# Banks_5_6.net
KiCad netlist of a schematic drawn in Altium Designer
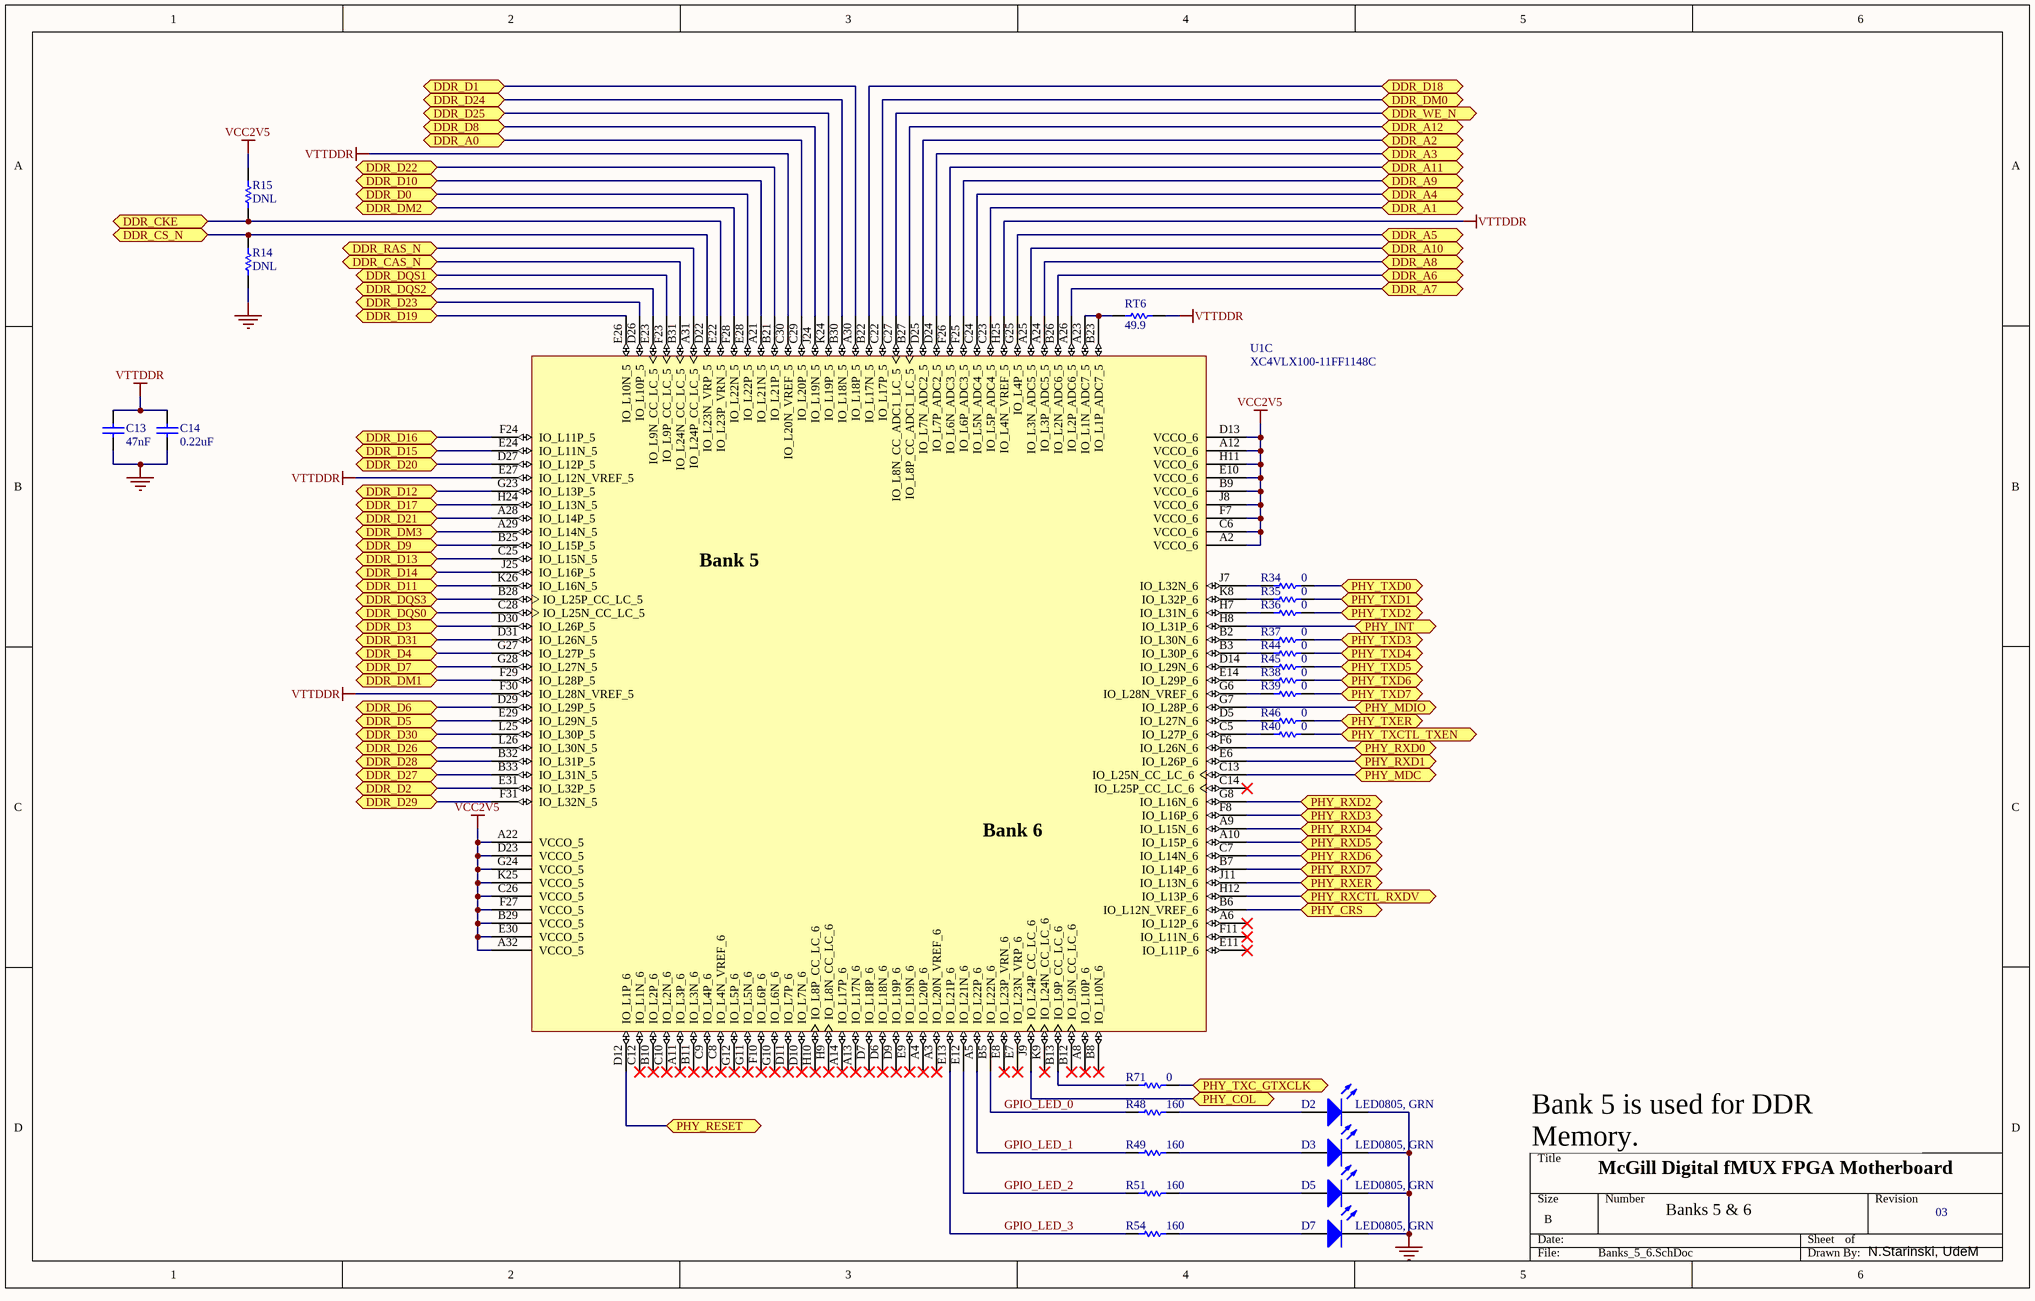
[diagram p0: Banks_5_6.SchDoc]

(export (version "E")
  (design (tool "Eeschema 10.0.6"))
  (components
    (comp (ref "C13")
      (value "47nF")
      (footprint "CC1005-0402")
      (description "Capacitor (Semiconductor SIM Model)")
      (fields (field (name "PUBLISHER") "Altium Limited"))
      (libsource (lib "Miscellaneous Devices") (part "Cap Semi"))
    )
    (comp (ref "C14")
      (value "0.22uF")
      (footprint "CC1608-0603")
      (description "Capacitor (Semiconductor SIM Model)")
      (fields (field (name "PUBLISHER") "Altium Limited"))
      (libsource (lib "Miscellaneous Devices") (part "Cap Semi"))
    )
    (comp (ref "D2")
      (value "LED0805, GRN")
      (footprint "SMD _LED")
      (description "LED 0805 LTST-C170GKT")
      (fields (field (name "PUBLISHER") "Altium Limited"))
      (libsource (lib "Miscellaneous Devices") (part "LED3"))
    )
    (comp (ref "D3")
      (value "LED0805, GRN")
      (footprint "SMD _LED")
      (description "LED 0805 LTST-C170GKT")
      (fields (field (name "PUBLISHER") "Altium Limited"))
      (libsource (lib "Miscellaneous Devices") (part "LED3"))
    )
    (comp (ref "D5")
      (value "LED0805, GRN")
      (footprint "SMD _LED")
      (description "LED 0805 LTST-C170GKT")
      (fields (field (name "PUBLISHER") "Altium Limited"))
      (libsource (lib "Miscellaneous Devices") (part "LED3"))
    )
    (comp (ref "D7")
      (value "LED0805, GRN")
      (footprint "SMD _LED")
      (description "LED 0805 LTST-C170GKT")
      (fields (field (name "PUBLISHER") "Altium Limited"))
      (libsource (lib "Miscellaneous Devices") (part "LED3"))
    )
    (comp (ref "R14")
      (value "DNL")
      (footprint "CR1608-0603")
      (description "Semiconductor Resistor")
      (fields (field (name "PUBLISHER") "Altium Limited"))
      (libsource (lib "Miscellaneous Devices 02") (part "Res Semi"))
    )
    (comp (ref "R15")
      (value "DNL")
      (footprint "CR1608-0603")
      (description "Semiconductor Resistor")
      (fields (field (name "PUBLISHER") "Altium Limited"))
      (libsource (lib "Miscellaneous Devices 02") (part "Res Semi"))
    )
    (comp (ref "R34")
      (value "0")
      (footprint "CR1608-0603")
      (description "Resistor 0603")
      (fields (field (name "PUBLISHER") "Altium Limited"))
      (libsource (lib "Miscellaneous Devices") (part "Res Semi"))
    )
    (comp (ref "R35")
      (value "0")
      (footprint "CR1608-0603")
      (description "Resistor 0603")
      (fields (field (name "PUBLISHER") "Altium Limited"))
      (libsource (lib "Miscellaneous Devices") (part "Res Semi"))
    )
    (comp (ref "R36")
      (value "0")
      (footprint "CR1608-0603")
      (description "Resistor 0603")
      (fields (field (name "PUBLISHER") "Altium Limited"))
      (libsource (lib "Miscellaneous Devices") (part "Res Semi"))
    )
    (comp (ref "R37")
      (value "0")
      (footprint "CR1608-0603")
      (description "Resistor 0603")
      (fields (field (name "PUBLISHER") "Altium Limited"))
      (libsource (lib "Miscellaneous Devices") (part "Res Semi"))
    )
    (comp (ref "R38")
      (value "0")
      (footprint "CR1608-0603")
      (description "Resistor 0603")
      (fields (field (name "PUBLISHER") "Altium Limited"))
      (libsource (lib "Miscellaneous Devices") (part "Res Semi"))
    )
    (comp (ref "R39")
      (value "0")
      (footprint "CR1608-0603")
      (description "Resistor 0603")
      (fields (field (name "PUBLISHER") "Altium Limited"))
      (libsource (lib "Miscellaneous Devices") (part "Res Semi"))
    )
    (comp (ref "R40")
      (value "0")
      (footprint "CR1608-0603")
      (description "Resistor 0603")
      (fields (field (name "PUBLISHER") "Altium Limited"))
      (libsource (lib "Miscellaneous Devices") (part "Res Semi"))
    )
    (comp (ref "R44")
      (value "0")
      (footprint "CR1608-0603")
      (description "Resistor 0603")
      (fields (field (name "PUBLISHER") "Altium Limited"))
      (libsource (lib "Miscellaneous Devices") (part "Res Semi"))
    )
    (comp (ref "R45")
      (value "0")
      (footprint "CR1608-0603")
      (description "Resistor 0603")
      (fields (field (name "PUBLISHER") "Altium Limited"))
      (libsource (lib "Miscellaneous Devices") (part "Res Semi"))
    )
    (comp (ref "R46")
      (value "0")
      (footprint "CR1608-0603")
      (description "Resistor 0603")
      (fields (field (name "PUBLISHER") "Altium Limited"))
      (libsource (lib "Miscellaneous Devices") (part "Res Semi"))
    )
    (comp (ref "R48")
      (value "160")
      (footprint "CR1608-0603")
      (description "Resistor 0603")
      (fields (field (name "PUBLISHER") "Altium Limited"))
      (libsource (lib "Miscellaneous Devices") (part "Res Semi"))
    )
    (comp (ref "R49")
      (value "160")
      (footprint "CR1608-0603")
      (description "Resistor 0603")
      (fields (field (name "PUBLISHER") "Altium Limited"))
      (libsource (lib "Miscellaneous Devices") (part "Res Semi"))
    )
    (comp (ref "R51")
      (value "160")
      (footprint "CR1608-0603")
      (description "Resistor 0603")
      (fields (field (name "PUBLISHER") "Altium Limited"))
      (libsource (lib "Miscellaneous Devices") (part "Res Semi"))
    )
    (comp (ref "R54")
      (value "160")
      (footprint "CR1608-0603")
      (description "Resistor 0603")
      (fields (field (name "PUBLISHER") "Altium Limited"))
      (libsource (lib "Miscellaneous Devices") (part "Res Semi"))
    )
    (comp (ref "R71")
      (value "0")
      (footprint "CR1608-0603")
      (description "Resistor 0603")
      (fields (field (name "PUBLISHER") "Altium Limited"))
      (libsource (lib "Miscellaneous Devices") (part "Res Semi"))
    )
    (comp (ref "RT6")
      (value "49.9")
      (footprint "CR1608-0603")
      (description "Resistor 0603")
      (fields (field (name "PUBLISHER") "Altium Limited"))
      (libsource (lib "Miscellaneous Devices 02") (part "Res Semi"))
    )
    (comp (ref "U1")
      (value "XC4VLX100-11FF1148C")
      (footprint "FF1148")
      (description "Xilinx Virtex-4 LX Platform FPGA, 1148-Ball FFBGA, Speed Grade 11, 768 User I/Os, Commercial Grade")
      (fields (field (name "PUBLISHER") "Altium Limited"))
      (libsource (lib "Xilinx Virtex-4") (part "XC4VLX100-11FF1148C"))
    )
  )
  (nets
    (net (code "1") (name "/DDR_A0") (class "Default")
      (node (ref "U1") (pin "C29") (pinfunction "IO_L20P_5_C29") (pintype "bidirectional"))
    )
    (net (code "2") (name "/DDR_A1") (class "Default")
      (node (ref "U1") (pin "C23") (pinfunction "IO_L5P_ADC4_5_C23") (pintype "bidirectional"))
    )
    (net (code "3") (name "/DDR_A2") (class "Default")
      (node (ref "U1") (pin "D25") (pinfunction "IO_L7N_ADC2_5_D25") (pintype "bidirectional"))
    )
    (net (code "4") (name "/DDR_A3") (class "Default")
      (node (ref "U1") (pin "D24") (pinfunction "IO_L7P_ADC2_5_D24") (pintype "bidirectional"))
    )
    (net (code "5") (name "/DDR_A4") (class "Default")
      (node (ref "U1") (pin "C24") (pinfunction "IO_L5N_ADC4_5_C24") (pintype "bidirectional"))
    )
    (net (code "6") (name "/DDR_A5") (class "Default")
      (node (ref "U1") (pin "G25") (pinfunction "IO_L4P_5_G25") (pintype "bidirectional"))
    )
    (net (code "7") (name "/DDR_A6") (class "Default")
      (node (ref "U1") (pin "B26") (pinfunction "IO_L2N_ADC6_5_B26") (pintype "bidirectional"))
    )
    (net (code "8") (name "/DDR_A7") (class "Default")
      (node (ref "U1") (pin "A26") (pinfunction "IO_L2P_ADC6_5_A26") (pintype "bidirectional"))
    )
    (net (code "9") (name "/DDR_A8") (class "Default")
      (node (ref "U1") (pin "A24") (pinfunction "IO_L3P_ADC5_5_A24") (pintype "bidirectional"))
    )
    (net (code "10") (name "/DDR_A9") (class "Default")
      (node (ref "U1") (pin "F25") (pinfunction "IO_L6P_ADC3_5_F25") (pintype "bidirectional"))
    )
    (net (code "11") (name "/DDR_A10") (class "Default")
      (node (ref "U1") (pin "A25") (pinfunction "IO_L3N_ADC5_5_A25") (pintype "bidirectional"))
    )
    (net (code "12") (name "/DDR_A11") (class "Default")
      (node (ref "U1") (pin "F26") (pinfunction "IO_L6N_ADC3_5_F26") (pintype "bidirectional"))
    )
    (net (code "13") (name "/DDR_A12") (class "Default")
      (node (ref "U1") (pin "B27") (pinfunction "IO_L8P_CC_ADC1_LC_5_B27") (pintype "bidirectional"))
    )
    (net (code "14") (name "/DDR_CAS_N") (class "Default")
      (node (ref "U1") (pin "B31") (pinfunction "IO_L24N_CC_LC_5_B31") (pintype "bidirectional"))
    )
    (net (code "15") (name "/DDR_CKE") (class "Default")
      (node (ref "R15") (pin "1") (pinfunction "1_1") (pintype "passive"))
      (node (ref "U1") (pin "E22") (pinfunction "IO_L23P_VRN_5_E22") (pintype "bidirectional"))
    )
    (net (code "16") (name "/DDR_CS_N") (class "Default")
      (node (ref "R14") (pin "2") (pinfunction "2_2") (pintype "passive"))
      (node (ref "U1") (pin "D22") (pinfunction "IO_L23N_VRP_5_D22") (pintype "bidirectional"))
    )
    (net (code "17") (name "/DDR_D0") (class "Default")
      (node (ref "U1") (pin "E28") (pinfunction "IO_L22P_5_E28") (pintype "bidirectional"))
    )
    (net (code "18") (name "/DDR_D1") (class "Default")
      (node (ref "U1") (pin "A30") (pinfunction "IO_L18P_5_A30") (pintype "bidirectional"))
    )
    (net (code "19") (name "/DDR_D2") (class "Default")
      (node (ref "U1") (pin "E31") (pinfunction "IO_L32P_5_E31") (pintype "bidirectional"))
    )
    (net (code "20") (name "/DDR_D3") (class "Default")
      (node (ref "U1") (pin "D30") (pinfunction "IO_L26P_5_D30") (pintype "bidirectional"))
    )
    (net (code "21") (name "/DDR_D4") (class "Default")
      (node (ref "U1") (pin "G27") (pinfunction "IO_L27P_5_G27") (pintype "bidirectional"))
    )
    (net (code "22") (name "/DDR_D5") (class "Default")
      (node (ref "U1") (pin "E29") (pinfunction "IO_L29N_5_E29") (pintype "bidirectional"))
    )
    (net (code "23") (name "/DDR_D6") (class "Default")
      (node (ref "U1") (pin "D29") (pinfunction "IO_L29P_5_D29") (pintype "bidirectional"))
    )
    (net (code "24") (name "/DDR_D7") (class "Default")
      (node (ref "U1") (pin "G28") (pinfunction "IO_L27N_5_G28") (pintype "bidirectional"))
    )
    (net (code "25") (name "/DDR_D8") (class "Default")
      (node (ref "U1") (pin "J24") (pinfunction "IO_L19N_5_J24") (pintype "bidirectional"))
    )
    (net (code "26") (name "/DDR_D9") (class "Default")
      (node (ref "U1") (pin "B25") (pinfunction "IO_L15P_5_B25") (pintype "bidirectional"))
    )
    (net (code "27") (name "/DDR_D10") (class "Default")
      (node (ref "U1") (pin "A21") (pinfunction "IO_L21N_5_A21") (pintype "bidirectional"))
    )
    (net (code "28") (name "/DDR_D11") (class "Default")
      (node (ref "U1") (pin "K26") (pinfunction "IO_L16N_5_K26") (pintype "bidirectional"))
    )
    (net (code "29") (name "/DDR_D12") (class "Default")
      (node (ref "U1") (pin "G23") (pinfunction "IO_L13P_5_G23") (pintype "bidirectional"))
    )
    (net (code "30") (name "/DDR_D13") (class "Default")
      (node (ref "U1") (pin "C25") (pinfunction "IO_L15N_5_C25") (pintype "bidirectional"))
    )
    (net (code "31") (name "/DDR_D14") (class "Default")
      (node (ref "U1") (pin "J25") (pinfunction "IO_L16P_5_J25") (pintype "bidirectional"))
    )
    (net (code "32") (name "/DDR_D15") (class "Default")
      (node (ref "U1") (pin "E24") (pinfunction "IO_L11N_5_E24") (pintype "bidirectional"))
    )
    (net (code "33") (name "/DDR_D16") (class "Default")
      (node (ref "U1") (pin "F24") (pinfunction "IO_L11P_5_F24") (pintype "bidirectional"))
    )
    (net (code "34") (name "/DDR_D17") (class "Default")
      (node (ref "U1") (pin "H24") (pinfunction "IO_L13N_5_H24") (pintype "bidirectional"))
    )
    (net (code "35") (name "/DDR_D18") (class "Default")
      (node (ref "U1") (pin "B22") (pinfunction "IO_L17N_5_B22") (pintype "bidirectional"))
    )
    (net (code "36") (name "/DDR_D19") (class "Default")
      (node (ref "U1") (pin "E26") (pinfunction "IO_L10N_5_E26") (pintype "bidirectional"))
    )
    (net (code "37") (name "/DDR_D20") (class "Default")
      (node (ref "U1") (pin "D27") (pinfunction "IO_L12P_5_D27") (pintype "bidirectional"))
    )
    (net (code "38") (name "/DDR_D21") (class "Default")
      (node (ref "U1") (pin "A28") (pinfunction "IO_L14P_5_A28") (pintype "bidirectional"))
    )
    (net (code "39") (name "/DDR_D22") (class "Default")
      (node (ref "U1") (pin "B21") (pinfunction "IO_L21P_5_B21") (pintype "bidirectional"))
    )
    (net (code "40") (name "/DDR_D23") (class "Default")
      (node (ref "U1") (pin "D26") (pinfunction "IO_L10P_5_D26") (pintype "bidirectional"))
    )
    (net (code "41") (name "/DDR_D24") (class "Default")
      (node (ref "U1") (pin "B30") (pinfunction "IO_L18N_5_B30") (pintype "bidirectional"))
    )
    (net (code "42") (name "/DDR_D25") (class "Default")
      (node (ref "U1") (pin "K24") (pinfunction "IO_L19P_5_K24") (pintype "bidirectional"))
    )
    (net (code "43") (name "/DDR_D26") (class "Default")
      (node (ref "U1") (pin "L26") (pinfunction "IO_L30N_5_L26") (pintype "bidirectional"))
    )
    (net (code "44") (name "/DDR_D27") (class "Default")
      (node (ref "U1") (pin "B33") (pinfunction "IO_L31N_5_B33") (pintype "bidirectional"))
    )
    (net (code "45") (name "/DDR_D28") (class "Default")
      (node (ref "U1") (pin "B32") (pinfunction "IO_L31P_5_B32") (pintype "bidirectional"))
    )
    (net (code "46") (name "/DDR_D29") (class "Default")
      (node (ref "U1") (pin "F31") (pinfunction "IO_L32N_5_F31") (pintype "bidirectional"))
    )
    (net (code "47") (name "/DDR_D30") (class "Default")
      (node (ref "U1") (pin "L25") (pinfunction "IO_L30P_5_L25") (pintype "bidirectional"))
    )
    (net (code "48") (name "/DDR_D31") (class "Default")
      (node (ref "U1") (pin "D31") (pinfunction "IO_L26N_5_D31") (pintype "bidirectional"))
    )
    (net (code "49") (name "/DDR_DM0") (class "Default")
      (node (ref "U1") (pin "C22") (pinfunction "IO_L17P_5_C22") (pintype "bidirectional"))
    )
    (net (code "50") (name "/DDR_DM1") (class "Default")
      (node (ref "U1") (pin "F29") (pinfunction "IO_L28P_5_F29") (pintype "bidirectional"))
    )
    (net (code "51") (name "/DDR_DM2") (class "Default")
      (node (ref "U1") (pin "F28") (pinfunction "IO_L22N_5_F28") (pintype "bidirectional"))
    )
    (net (code "52") (name "/DDR_DM3") (class "Default")
      (node (ref "U1") (pin "A29") (pinfunction "IO_L14N_5_A29") (pintype "bidirectional"))
    )
    (net (code "53") (name "/DDR_DQS0") (class "Default")
      (node (ref "U1") (pin "C28") (pinfunction "IO_L25N_CC_LC_5_C28") (pintype "bidirectional"))
    )
    (net (code "54") (name "/DDR_DQS1") (class "Default")
      (node (ref "U1") (pin "F23") (pinfunction "IO_L9P_CC_LC_5_F23") (pintype "bidirectional"))
    )
    (net (code "55") (name "/DDR_DQS2") (class "Default")
      (node (ref "U1") (pin "E23") (pinfunction "IO_L9N_CC_LC_5_E23") (pintype "bidirectional"))
    )
    (net (code "56") (name "/DDR_DQS3") (class "Default")
      (node (ref "U1") (pin "B28") (pinfunction "IO_L25P_CC_LC_5_B28") (pintype "bidirectional"))
    )
    (net (code "57") (name "/DDR_RAS_N") (class "Default")
      (node (ref "U1") (pin "A31") (pinfunction "IO_L24P_CC_LC_5_A31") (pintype "bidirectional"))
    )
    (net (code "58") (name "/DDR_WE_N") (class "Default")
      (node (ref "U1") (pin "C27") (pinfunction "IO_L8N_CC_ADC1_LC_5_C27") (pintype "bidirectional"))
    )
    (net (code "59") (name "/GPIO_LED_0") (class "Default")
      (node (ref "R48") (pin "1") (pinfunction "1_1") (pintype "passive"))
      (node (ref "U1") (pin "B5") (pinfunction "IO_L22N_6_B5") (pintype "bidirectional"))
    )
    (net (code "60") (name "/GPIO_LED_1") (class "Default")
      (node (ref "R49") (pin "1") (pinfunction "1_1") (pintype "passive"))
      (node (ref "U1") (pin "A5") (pinfunction "IO_L22P_6_A5") (pintype "bidirectional"))
    )
    (net (code "61") (name "/GPIO_LED_2") (class "Default")
      (node (ref "R51") (pin "1") (pinfunction "1_1") (pintype "passive"))
      (node (ref "U1") (pin "E12") (pinfunction "IO_L21N_6_E12") (pintype "bidirectional"))
    )
    (net (code "62") (name "/GPIO_LED_3") (class "Default")
      (node (ref "R54") (pin "1") (pinfunction "1_1") (pintype "passive"))
      (node (ref "U1") (pin "E13") (pinfunction "IO_L21P_6_E13") (pintype "bidirectional"))
    )
    (net (code "63") (name "/PHY_COL") (class "Default")
      (node (ref "U1") (pin "J9") (pinfunction "IO_L24P_CC_LC_6_J9") (pintype "bidirectional"))
    )
    (net (code "64") (name "/PHY_CRS") (class "Default")
      (node (ref "U1") (pin "B6") (pinfunction "IO_L12N_VREF_6_B6") (pintype "bidirectional"))
    )
    (net (code "65") (name "/PHY_INT") (class "Default")
      (node (ref "U1") (pin "H8") (pinfunction "IO_L31P_6_H8") (pintype "bidirectional"))
    )
    (net (code "66") (name "/PHY_MDC") (class "Default")
      (node (ref "U1") (pin "C13") (pinfunction "IO_L25N_CC_LC_6_C13") (pintype "bidirectional"))
    )
    (net (code "67") (name "/PHY_MDIO") (class "Default")
      (node (ref "U1") (pin "G7") (pinfunction "IO_L28P_6_G7") (pintype "bidirectional"))
    )
    (net (code "68") (name "/PHY_RESET") (class "Default")
      (node (ref "U1") (pin "D12") (pinfunction "IO_L1P_6_D12") (pintype "bidirectional"))
    )
    (net (code "69") (name "/PHY_RXCTL_RXDV") (class "Default")
      (node (ref "U1") (pin "H12") (pinfunction "IO_L13P_6_H12") (pintype "bidirectional"))
    )
    (net (code "70") (name "/PHY_RXD0") (class "Default")
      (node (ref "U1") (pin "F6") (pinfunction "IO_L26N_6_F6") (pintype "bidirectional"))
    )
    (net (code "71") (name "/PHY_RXD1") (class "Default")
      (node (ref "U1") (pin "E6") (pinfunction "IO_L26P_6_E6") (pintype "bidirectional"))
    )
    (net (code "72") (name "/PHY_RXD2") (class "Default")
      (node (ref "U1") (pin "G8") (pinfunction "IO_L16N_6_G8") (pintype "bidirectional"))
    )
    (net (code "73") (name "/PHY_RXD3") (class "Default")
      (node (ref "U1") (pin "F8") (pinfunction "IO_L16P_6_F8") (pintype "bidirectional"))
    )
    (net (code "74") (name "/PHY_RXD4") (class "Default")
      (node (ref "U1") (pin "A9") (pinfunction "IO_L15N_6_A9") (pintype "bidirectional"))
    )
    (net (code "75") (name "/PHY_RXD5") (class "Default")
      (node (ref "U1") (pin "A10") (pinfunction "IO_L15P_6_A10") (pintype "bidirectional"))
    )
    (net (code "76") (name "/PHY_RXD6") (class "Default")
      (node (ref "U1") (pin "C7") (pinfunction "IO_L14N_6_C7") (pintype "bidirectional"))
    )
    (net (code "77") (name "/PHY_RXD7") (class "Default")
      (node (ref "U1") (pin "B7") (pinfunction "IO_L14P_6_B7") (pintype "bidirectional"))
    )
    (net (code "78") (name "/PHY_RXER") (class "Default")
      (node (ref "U1") (pin "J11") (pinfunction "IO_L13N_6_J11") (pintype "bidirectional"))
    )
    (net (code "79") (name "/PHY_TXCTL_TXEN") (class "Default")
      (node (ref "R40") (pin "2") (pinfunction "2_2") (pintype "passive"))
    )
    (net (code "80") (name "/PHY_TXC_GTXCLK") (class "Default")
      (node (ref "R71") (pin "2") (pinfunction "2_2") (pintype "passive"))
    )
    (net (code "81") (name "/PHY_TXD0") (class "Default")
      (node (ref "R34") (pin "2") (pinfunction "2_2") (pintype "passive"))
    )
    (net (code "82") (name "/PHY_TXD1") (class "Default")
      (node (ref "R35") (pin "2") (pinfunction "2_2") (pintype "passive"))
    )
    (net (code "83") (name "/PHY_TXD2") (class "Default")
      (node (ref "R36") (pin "2") (pinfunction "2_2") (pintype "passive"))
    )
    (net (code "84") (name "/PHY_TXD3") (class "Default")
      (node (ref "R37") (pin "2") (pinfunction "2_2") (pintype "passive"))
    )
    (net (code "85") (name "/PHY_TXD4") (class "Default")
      (node (ref "R44") (pin "2") (pinfunction "2_2") (pintype "passive"))
    )
    (net (code "86") (name "/PHY_TXD5") (class "Default")
      (node (ref "R45") (pin "2") (pinfunction "2_2") (pintype "passive"))
    )
    (net (code "87") (name "/PHY_TXD6") (class "Default")
      (node (ref "R38") (pin "2") (pinfunction "2_2") (pintype "passive"))
    )
    (net (code "88") (name "/PHY_TXD7") (class "Default")
      (node (ref "R39") (pin "2") (pinfunction "2_2") (pintype "passive"))
    )
    (net (code "89") (name "/PHY_TXER") (class "Default")
      (node (ref "R46") (pin "2") (pinfunction "2_2") (pintype "passive"))
    )
    (net (code "90") (name "GND") (class "Default")
      (node (ref "C13") (pin "1") (pinfunction "1_1") (pintype "passive"))
      (node (ref "C14") (pin "1") (pinfunction "1_1") (pintype "passive"))
      (node (ref "D2") (pin "2") (pinfunction "K_2") (pintype "passive"))
      (node (ref "D3") (pin "2") (pinfunction "K_2") (pintype "passive"))
      (node (ref "D5") (pin "2") (pinfunction "K_2") (pintype "passive"))
      (node (ref "D7") (pin "2") (pinfunction "K_2") (pintype "passive"))
      (node (ref "R14") (pin "1") (pinfunction "1_1") (pintype "passive"))
    )
    (net (code "91") (name "Net-(D2-A)") (class "Default")
      (node (ref "D2") (pin "1") (pinfunction "A_1") (pintype "passive"))
      (node (ref "R48") (pin "2") (pinfunction "2_2") (pintype "passive"))
    )
    (net (code "92") (name "Net-(D3-A)") (class "Default")
      (node (ref "D3") (pin "1") (pinfunction "A_1") (pintype "passive"))
      (node (ref "R49") (pin "2") (pinfunction "2_2") (pintype "passive"))
    )
    (net (code "93") (name "Net-(D5-A)") (class "Default")
      (node (ref "D5") (pin "1") (pinfunction "A_1") (pintype "passive"))
      (node (ref "R51") (pin "2") (pinfunction "2_2") (pintype "passive"))
    )
    (net (code "94") (name "Net-(D7-A)") (class "Default")
      (node (ref "D7") (pin "1") (pinfunction "A_1") (pintype "passive"))
      (node (ref "R54") (pin "2") (pinfunction "2_2") (pintype "passive"))
    )
    (net (code "95") (name "Net-(U1C-IO_L1N_ADC7_5)") (class "Default")
      (node (ref "RT6") (pin "1") (pinfunction "1_1") (pintype "passive"))
      (node (ref "U1") (pin "A23") (pinfunction "IO_L1N_ADC7_5_A23") (pintype "bidirectional"))
      (node (ref "U1") (pin "B23") (pinfunction "IO_L1P_ADC7_5_B23") (pintype "bidirectional"))
    )
    (net (code "96") (name "Net-(U1C-IO_L9P_CC_LC_6)") (class "Default")
      (node (ref "R71") (pin "1") (pinfunction "1_1") (pintype "passive"))
      (node (ref "U1") (pin "B13") (pinfunction "IO_L9P_CC_LC_6_B13") (pintype "bidirectional"))
    )
    (net (code "97") (name "Net-(U1C-IO_L27N_6)") (class "Default")
      (node (ref "R46") (pin "1") (pinfunction "1_1") (pintype "passive"))
      (node (ref "U1") (pin "D5") (pinfunction "IO_L27N_6_D5") (pintype "bidirectional"))
    )
    (net (code "98") (name "Net-(U1C-IO_L27P_6)") (class "Default")
      (node (ref "R40") (pin "1") (pinfunction "1_1") (pintype "passive"))
      (node (ref "U1") (pin "C5") (pinfunction "IO_L27P_6_C5") (pintype "bidirectional"))
    )
    (net (code "99") (name "Net-(U1C-IO_L28N_VREF_6)") (class "Default")
      (node (ref "R39") (pin "1") (pinfunction "1_1") (pintype "passive"))
      (node (ref "U1") (pin "G6") (pinfunction "IO_L28N_VREF_6_G6") (pintype "bidirectional"))
    )
    (net (code "100") (name "Net-(U1C-IO_L29N_6)") (class "Default")
      (node (ref "R45") (pin "1") (pinfunction "1_1") (pintype "passive"))
      (node (ref "U1") (pin "D14") (pinfunction "IO_L29N_6_D14") (pintype "bidirectional"))
    )
    (net (code "101") (name "Net-(U1C-IO_L29P_6)") (class "Default")
      (node (ref "R38") (pin "1") (pinfunction "1_1") (pintype "passive"))
      (node (ref "U1") (pin "E14") (pinfunction "IO_L29P_6_E14") (pintype "bidirectional"))
    )
    (net (code "102") (name "Net-(U1C-IO_L30N_6)") (class "Default")
      (node (ref "R37") (pin "1") (pinfunction "1_1") (pintype "passive"))
      (node (ref "U1") (pin "B2") (pinfunction "IO_L30N_6_B2") (pintype "bidirectional"))
    )
    (net (code "103") (name "Net-(U1C-IO_L30P_6)") (class "Default")
      (node (ref "R44") (pin "1") (pinfunction "1_1") (pintype "passive"))
      (node (ref "U1") (pin "B3") (pinfunction "IO_L30P_6_B3") (pintype "bidirectional"))
    )
    (net (code "104") (name "Net-(U1C-IO_L31N_6)") (class "Default")
      (node (ref "R36") (pin "1") (pinfunction "1_1") (pintype "passive"))
      (node (ref "U1") (pin "H7") (pinfunction "IO_L31N_6_H7") (pintype "bidirectional"))
    )
    (net (code "105") (name "Net-(U1C-IO_L32N_6)") (class "Default")
      (node (ref "R34") (pin "1") (pinfunction "1_1") (pintype "passive"))
      (node (ref "U1") (pin "J7") (pinfunction "IO_L32N_6_J7") (pintype "bidirectional"))
    )
    (net (code "106") (name "Net-(U1C-IO_L32P_6)") (class "Default")
      (node (ref "R35") (pin "1") (pinfunction "1_1") (pintype "passive"))
      (node (ref "U1") (pin "K8") (pinfunction "IO_L32P_6_K8") (pintype "bidirectional"))
    )
    (net (code "107") (name "VCC2V5") (class "Default")
      (node (ref "R15") (pin "2") (pinfunction "2_2") (pintype "passive"))
      (node (ref "U1") (pin "A12") (pinfunction "VCCO_6_A12") (pintype "power_in"))
      (node (ref "U1") (pin "A2") (pinfunction "VCCO_6_A2") (pintype "power_in"))
      (node (ref "U1") (pin "A22") (pinfunction "VCCO_5_A22") (pintype "power_in"))
      (node (ref "U1") (pin "A32") (pinfunction "VCCO_5_A32") (pintype "power_in"))
      (node (ref "U1") (pin "B29") (pinfunction "VCCO_5_B29") (pintype "power_in"))
      (node (ref "U1") (pin "B9") (pinfunction "VCCO_6_B9") (pintype "power_in"))
      (node (ref "U1") (pin "C26") (pinfunction "VCCO_5_C26") (pintype "power_in"))
      (node (ref "U1") (pin "C6") (pinfunction "VCCO_6_C6") (pintype "power_in"))
      (node (ref "U1") (pin "D13") (pinfunction "VCCO_6_D13") (pintype "power_in"))
      (node (ref "U1") (pin "D23") (pinfunction "VCCO_5_D23") (pintype "power_in"))
      (node (ref "U1") (pin "E10") (pinfunction "VCCO_6_E10") (pintype "power_in"))
      (node (ref "U1") (pin "E30") (pinfunction "VCCO_5_E30") (pintype "power_in"))
      (node (ref "U1") (pin "F27") (pinfunction "VCCO_5_F27") (pintype "power_in"))
      (node (ref "U1") (pin "F7") (pinfunction "VCCO_6_F7") (pintype "power_in"))
      (node (ref "U1") (pin "G24") (pinfunction "VCCO_5_G24") (pintype "power_in"))
      (node (ref "U1") (pin "H11") (pinfunction "VCCO_6_H11") (pintype "power_in"))
      (node (ref "U1") (pin "J8") (pinfunction "VCCO_6_J8") (pintype "power_in"))
      (node (ref "U1") (pin "K25") (pinfunction "VCCO_5_K25") (pintype "power_in"))
    )
    (net (code "108") (name "VTTDDR") (class "Default")
      (node (ref "C13") (pin "2") (pinfunction "2_2") (pintype "passive"))
      (node (ref "C14") (pin "2") (pinfunction "2_2") (pintype "passive"))
      (node (ref "RT6") (pin "2") (pinfunction "2_2") (pintype "passive"))
      (node (ref "U1") (pin "C30") (pinfunction "IO_L20N_VREF_5_C30") (pintype "bidirectional"))
      (node (ref "U1") (pin "E27") (pinfunction "IO_L12N_VREF_5_E27") (pintype "bidirectional"))
      (node (ref "U1") (pin "F30") (pinfunction "IO_L28N_VREF_5_F30") (pintype "bidirectional"))
      (node (ref "U1") (pin "H25") (pinfunction "IO_L4N_VREF_5_H25") (pintype "bidirectional"))
    )
    (net (code "109") (name "unconnected-(U1C-IO_L1N_6-PadC12)") (class "Default")
      (node (ref "U1") (pin "C12") (pinfunction "IO_L1N_6_C12") (pintype "bidirectional+no_connect"))
    )
    (net (code "110") (name "unconnected-(U1C-IO_L2N_6-PadC10)") (class "Default")
      (node (ref "U1") (pin "C10") (pinfunction "IO_L2N_6_C10") (pintype "bidirectional+no_connect"))
    )
    (net (code "111") (name "unconnected-(U1C-IO_L2P_6-PadB10)") (class "Default")
      (node (ref "U1") (pin "B10") (pinfunction "IO_L2P_6_B10") (pintype "bidirectional+no_connect"))
    )
    (net (code "112") (name "unconnected-(U1C-IO_L3N_6-PadB11)") (class "Default")
      (node (ref "U1") (pin "B11") (pinfunction "IO_L3N_6_B11") (pintype "bidirectional+no_connect"))
    )
    (net (code "113") (name "unconnected-(U1C-IO_L3P_6-PadA11)") (class "Default")
      (node (ref "U1") (pin "A11") (pinfunction "IO_L3P_6_A11") (pintype "bidirectional+no_connect"))
    )
    (net (code "114") (name "unconnected-(U1C-IO_L4N_VREF_6-PadC8)") (class "Default")
      (node (ref "U1") (pin "C8") (pinfunction "IO_L4N_VREF_6_C8") (pintype "bidirectional+no_connect"))
    )
    (net (code "115") (name "unconnected-(U1C-IO_L4P_6-PadC9)") (class "Default")
      (node (ref "U1") (pin "C9") (pinfunction "IO_L4P_6_C9") (pintype "bidirectional+no_connect"))
    )
    (net (code "116") (name "unconnected-(U1C-IO_L5N_6-PadG11)") (class "Default")
      (node (ref "U1") (pin "G11") (pinfunction "IO_L5N_6_G11") (pintype "bidirectional+no_connect"))
    )
    (net (code "117") (name "unconnected-(U1C-IO_L5P_6-PadG12)") (class "Default")
      (node (ref "U1") (pin "G12") (pinfunction "IO_L5P_6_G12") (pintype "bidirectional+no_connect"))
    )
    (net (code "118") (name "unconnected-(U1C-IO_L6N_6-PadG10)") (class "Default")
      (node (ref "U1") (pin "G10") (pinfunction "IO_L6N_6_G10") (pintype "bidirectional+no_connect"))
    )
    (net (code "119") (name "unconnected-(U1C-IO_L6P_6-PadF10)") (class "Default")
      (node (ref "U1") (pin "F10") (pinfunction "IO_L6P_6_F10") (pintype "bidirectional+no_connect"))
    )
    (net (code "120") (name "unconnected-(U1C-IO_L7N_6-PadD10)") (class "Default")
      (node (ref "U1") (pin "D10") (pinfunction "IO_L7N_6_D10") (pintype "bidirectional+no_connect"))
    )
    (net (code "121") (name "unconnected-(U1C-IO_L7P_6-PadD11)") (class "Default")
      (node (ref "U1") (pin "D11") (pinfunction "IO_L7P_6_D11") (pintype "bidirectional+no_connect"))
    )
    (net (code "122") (name "unconnected-(U1C-IO_L8N_CC_LC_6-PadH9)") (class "Default")
      (node (ref "U1") (pin "H9") (pinfunction "IO_L8N_CC_LC_6_H9") (pintype "bidirectional+no_connect"))
    )
    (net (code "123") (name "unconnected-(U1C-IO_L8P_CC_LC_6-PadH10)") (class "Default")
      (node (ref "U1") (pin "H10") (pinfunction "IO_L8P_CC_LC_6_H10") (pintype "bidirectional+no_connect"))
    )
    (net (code "124") (name "unconnected-(U1C-IO_L9N_CC_LC_6-PadB12)") (class "Default")
      (node (ref "U1") (pin "B12") (pinfunction "IO_L9N_CC_LC_6_B12") (pintype "bidirectional+no_connect"))
    )
    (net (code "125") (name "unconnected-(U1C-IO_L10N_6-PadB8)") (class "Default")
      (node (ref "U1") (pin "B8") (pinfunction "IO_L10N_6_B8") (pintype "bidirectional+no_connect"))
    )
    (net (code "126") (name "unconnected-(U1C-IO_L10P_6-PadA8)") (class "Default")
      (node (ref "U1") (pin "A8") (pinfunction "IO_L10P_6_A8") (pintype "bidirectional+no_connect"))
    )
    (net (code "127") (name "unconnected-(U1C-IO_L11N_6-PadF11)") (class "Default")
      (node (ref "U1") (pin "F11") (pinfunction "IO_L11N_6_F11") (pintype "bidirectional+no_connect"))
    )
    (net (code "128") (name "unconnected-(U1C-IO_L11P_6-PadE11)") (class "Default")
      (node (ref "U1") (pin "E11") (pinfunction "IO_L11P_6_E11") (pintype "bidirectional+no_connect"))
    )
    (net (code "129") (name "unconnected-(U1C-IO_L12P_6-PadA6)") (class "Default")
      (node (ref "U1") (pin "A6") (pinfunction "IO_L12P_6_A6") (pintype "bidirectional+no_connect"))
    )
    (net (code "130") (name "unconnected-(U1C-IO_L17N_6-PadA13)") (class "Default")
      (node (ref "U1") (pin "A13") (pinfunction "IO_L17N_6_A13") (pintype "bidirectional+no_connect"))
    )
    (net (code "131") (name "unconnected-(U1C-IO_L17P_6-PadA14)") (class "Default")
      (node (ref "U1") (pin "A14") (pinfunction "IO_L17P_6_A14") (pintype "bidirectional+no_connect"))
    )
    (net (code "132") (name "unconnected-(U1C-IO_L18N_6-PadD6)") (class "Default")
      (node (ref "U1") (pin "D6") (pinfunction "IO_L18N_6_D6") (pintype "bidirectional+no_connect"))
    )
    (net (code "133") (name "unconnected-(U1C-IO_L18P_6-PadD7)") (class "Default")
      (node (ref "U1") (pin "D7") (pinfunction "IO_L18P_6_D7") (pintype "bidirectional+no_connect"))
    )
    (net (code "134") (name "unconnected-(U1C-IO_L19N_6-PadE9)") (class "Default")
      (node (ref "U1") (pin "E9") (pinfunction "IO_L19N_6_E9") (pintype "bidirectional+no_connect"))
    )
    (net (code "135") (name "unconnected-(U1C-IO_L19P_6-PadD9)") (class "Default")
      (node (ref "U1") (pin "D9") (pinfunction "IO_L19P_6_D9") (pintype "bidirectional+no_connect"))
    )
    (net (code "136") (name "unconnected-(U1C-IO_L20N_VREF_6-PadA3)") (class "Default")
      (node (ref "U1") (pin "A3") (pinfunction "IO_L20N_VREF_6_A3") (pintype "bidirectional+no_connect"))
    )
    (net (code "137") (name "unconnected-(U1C-IO_L20P_6-PadA4)") (class "Default")
      (node (ref "U1") (pin "A4") (pinfunction "IO_L20P_6_A4") (pintype "bidirectional+no_connect"))
    )
    (net (code "138") (name "unconnected-(U1C-IO_L23N_VRP_6-PadE7)") (class "Default")
      (node (ref "U1") (pin "E7") (pinfunction "IO_L23N_VRP_6_E7") (pintype "bidirectional+no_connect"))
    )
    (net (code "139") (name "unconnected-(U1C-IO_L23P_VRN_6-PadE8)") (class "Default")
      (node (ref "U1") (pin "E8") (pinfunction "IO_L23P_VRN_6_E8") (pintype "bidirectional+no_connect"))
    )
    (net (code "140") (name "unconnected-(U1C-IO_L24N_CC_LC_6-PadK9)") (class "Default")
      (node (ref "U1") (pin "K9") (pinfunction "IO_L24N_CC_LC_6_K9") (pintype "bidirectional+no_connect"))
    )
    (net (code "141") (name "unconnected-(U1C-IO_L25P_CC_LC_6-PadC14)") (class "Default")
      (node (ref "U1") (pin "C14") (pinfunction "IO_L25P_CC_LC_6_C14") (pintype "bidirectional+no_connect"))
    )
  )
)
